# SCH_led_button_2026-04-28.net
KiCad netlist of a schematic drawn in EasyEDA
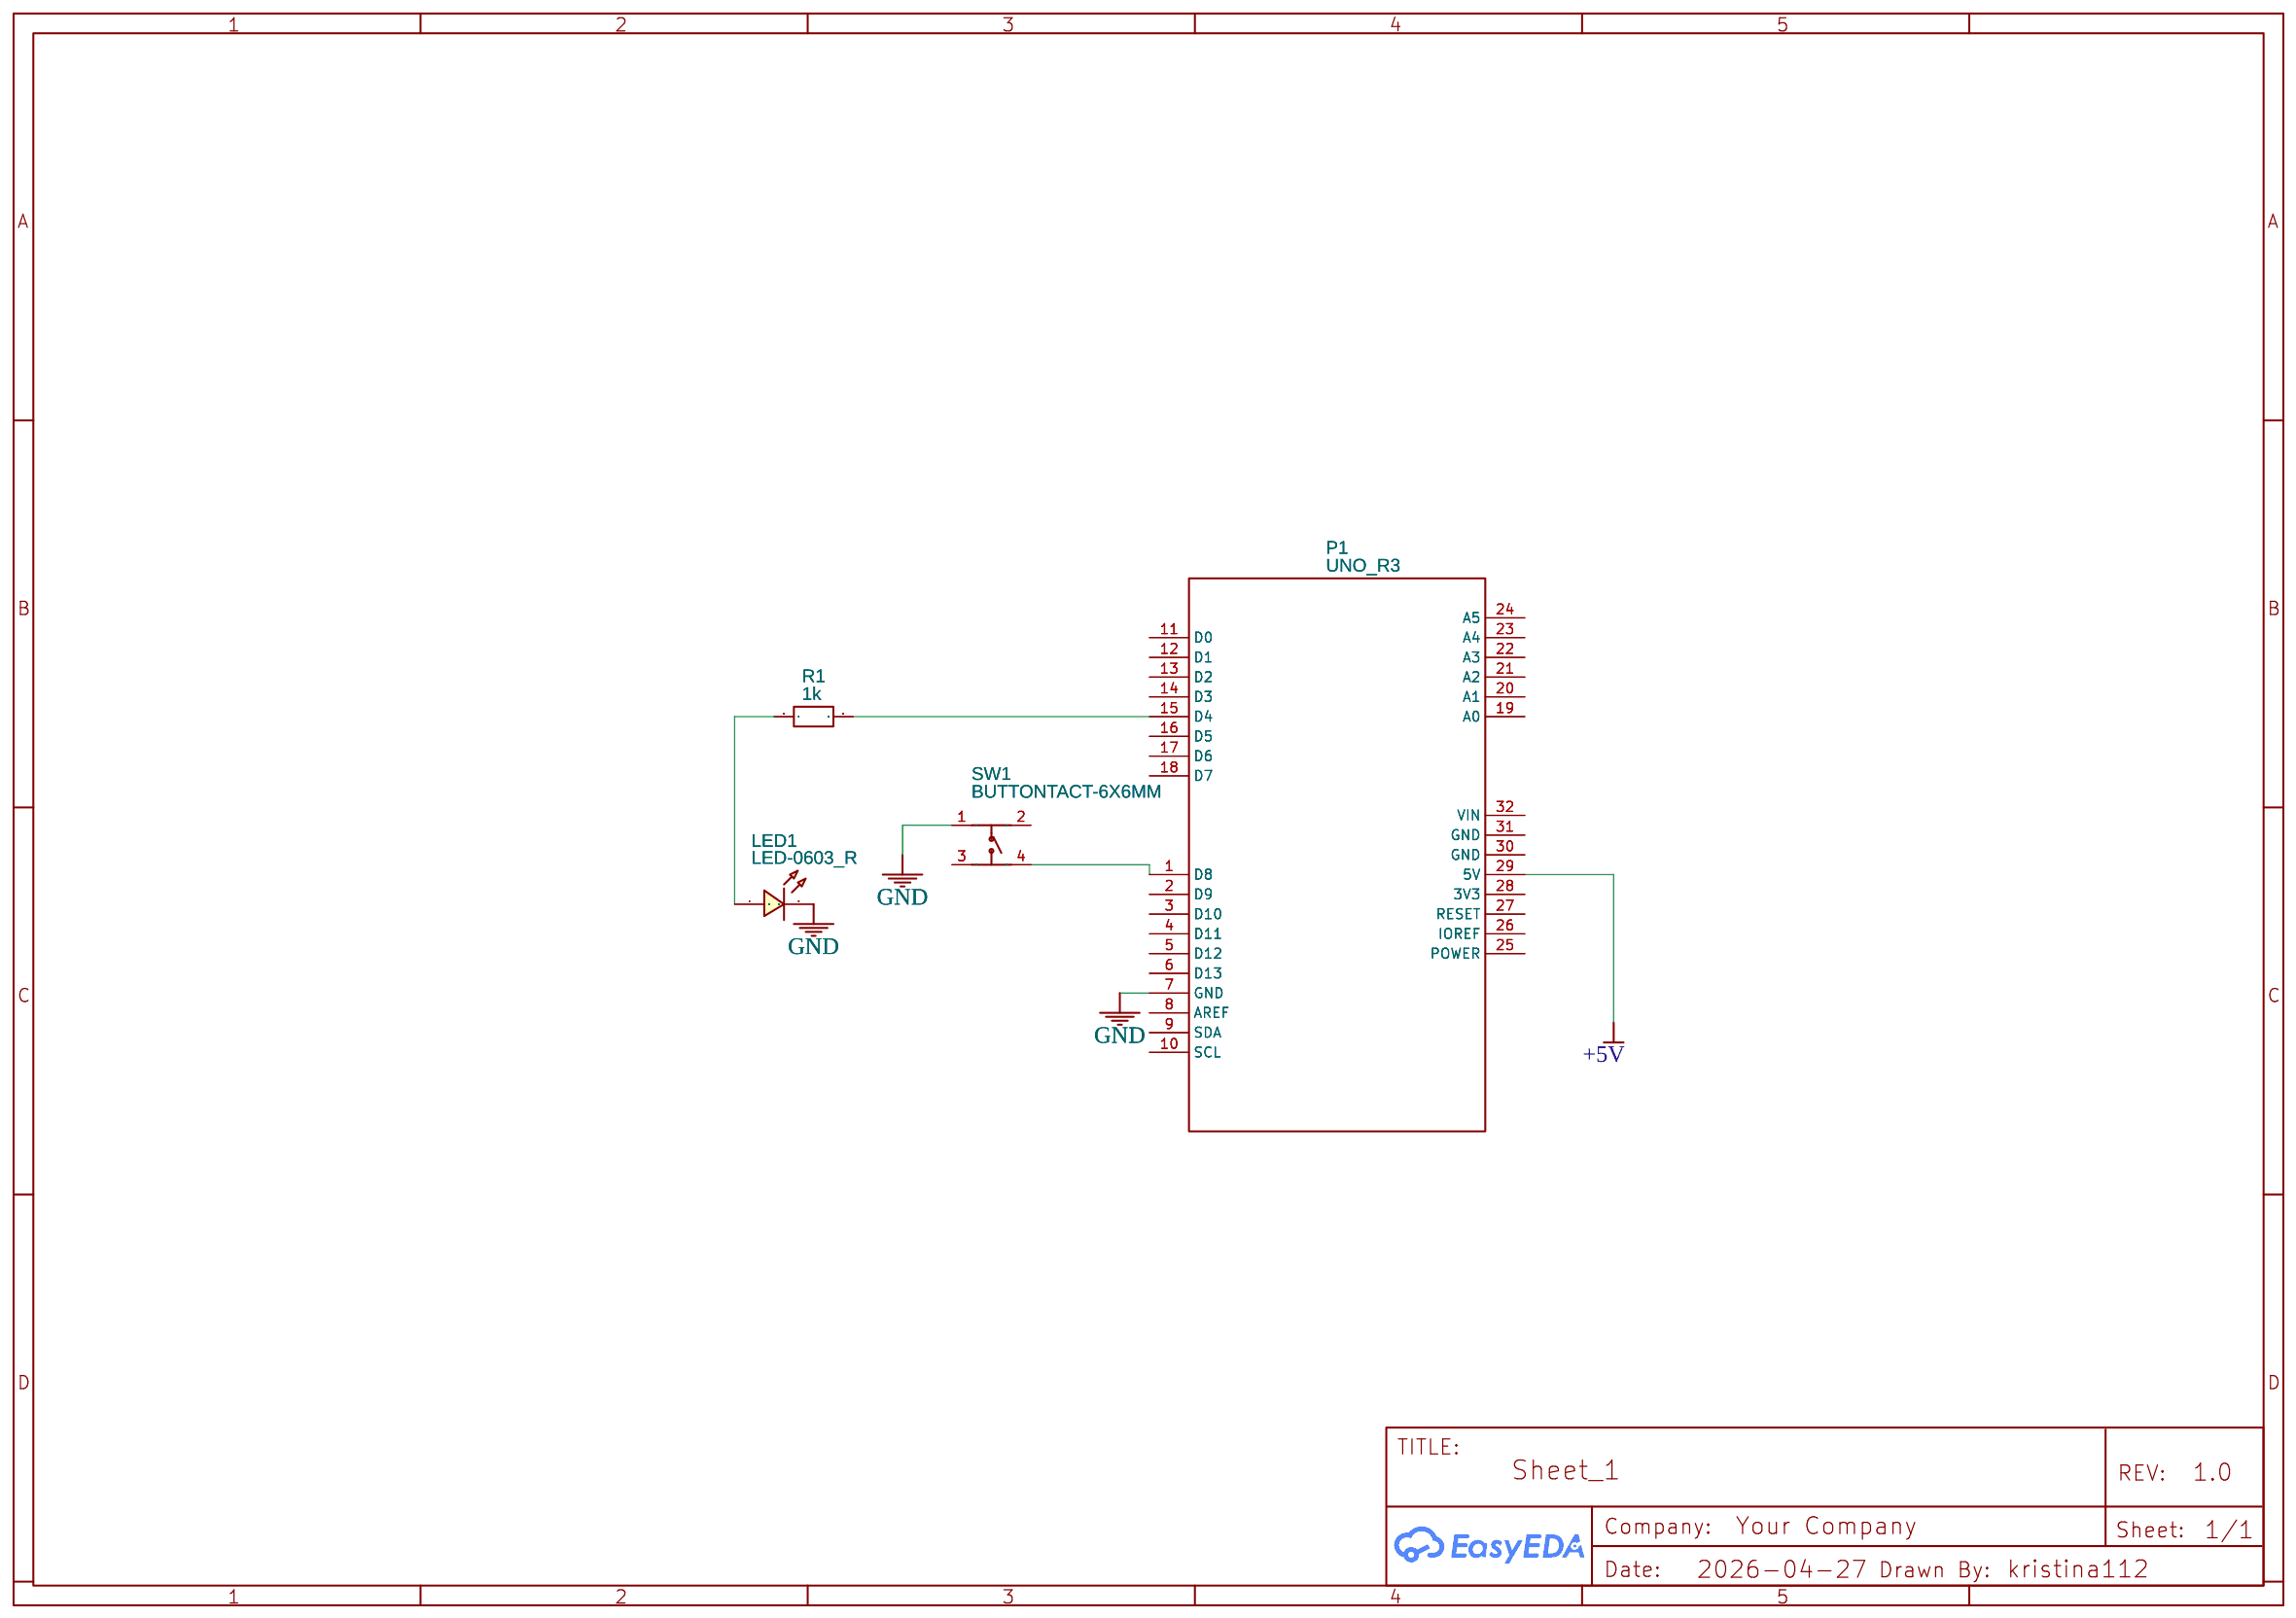
[diagram p0: schematic sheet]

(export (version "E")
  (design (tool "Eeschema 10.0.6"))
  (components
    (comp (ref "LED1")
      (value "LED-0603_R")
      (fields
        (field (name "Manufacturer Part") "19-217/R6C-AL1M2VY/3T")
        (field (name "Manufacturer") "EVERLIGHT(台湾亿光)")
      )
      (libsource (lib "") (part "LED-0603_R"))
    )
    (comp (ref "P1") (value "UNO_R3") (libsource (lib "") (part "UNO_R3")))
    (comp (ref "R1") (value "1k") (libsource (lib "") (part "R_0603_EU")))
    (comp (ref "SW1")
      (value "BUTTONTACT-6X6MM")
      (fields (field (name "Manufacturer Part") "Buttontact-6x6mm"))
      (libsource (lib "") (part "BUTTONTACT-6X6MM"))
    )
  )
  (nets
    (net (code "1") (name "+5V") (class "Default")
      (node (ref "P1") (pin "29") (pinfunction "5V_29") (pintype "unspecified"))
    )
    (net (code "2") (name "GND") (class "Default")
      (node (ref "LED1") (pin "2") (pinfunction "2_2") (pintype "unspecified"))
      (node (ref "P1") (pin "7") (pinfunction "GND_7") (pintype "unspecified"))
      (node (ref "SW1") (pin "1") (pinfunction "A_1") (pintype "unspecified"))
    )
    (net (code "3") (name "Net-(LED1-Pad1)") (class "Default")
      (node (ref "LED1") (pin "1") (pinfunction "1_1") (pintype "unspecified"))
      (node (ref "R1") (pin "1") (pinfunction "1_1") (pintype "unspecified"))
    )
    (net (code "4") (name "Net-(P1-D4)") (class "Default")
      (node (ref "P1") (pin "15") (pinfunction "D4_15") (pintype "unspecified"))
      (node (ref "R1") (pin "2") (pinfunction "2_2") (pintype "unspecified"))
    )
    (net (code "5") (name "Net-(P1-D8)") (class "Default")
      (node (ref "P1") (pin "1") (pinfunction "D8_1") (pintype "unspecified"))
      (node (ref "SW1") (pin "4") (pinfunction "D_4") (pintype "unspecified"))
    )
    (net (code "6") (name "unconnected-(P1-3V3-Pad28)") (class "Default")
      (node (ref "P1") (pin "28") (pinfunction "3V3_28") (pintype "unspecified"))
    )
    (net (code "7") (name "unconnected-(P1-A0-Pad19)") (class "Default")
      (node (ref "P1") (pin "19") (pinfunction "A0_19") (pintype "unspecified"))
    )
    (net (code "8") (name "unconnected-(P1-A1-Pad20)") (class "Default")
      (node (ref "P1") (pin "20") (pinfunction "A1_20") (pintype "unspecified"))
    )
    (net (code "9") (name "unconnected-(P1-A2-Pad21)") (class "Default")
      (node (ref "P1") (pin "21") (pinfunction "A2_21") (pintype "unspecified"))
    )
    (net (code "10") (name "unconnected-(P1-A3-Pad22)") (class "Default")
      (node (ref "P1") (pin "22") (pinfunction "A3_22") (pintype "unspecified"))
    )
    (net (code "11") (name "unconnected-(P1-A4-Pad23)") (class "Default")
      (node (ref "P1") (pin "23") (pinfunction "A4_23") (pintype "unspecified"))
    )
    (net (code "12") (name "unconnected-(P1-A5-Pad24)") (class "Default")
      (node (ref "P1") (pin "24") (pinfunction "A5_24") (pintype "unspecified"))
    )
    (net (code "13") (name "unconnected-(P1-AREF-Pad8)") (class "Default")
      (node (ref "P1") (pin "8") (pinfunction "AREF_8") (pintype "unspecified"))
    )
    (net (code "14") (name "unconnected-(P1-D0-Pad11)") (class "Default")
      (node (ref "P1") (pin "11") (pinfunction "D0_11") (pintype "unspecified"))
    )
    (net (code "15") (name "unconnected-(P1-D1-Pad12)") (class "Default")
      (node (ref "P1") (pin "12") (pinfunction "D1_12") (pintype "unspecified"))
    )
    (net (code "16") (name "unconnected-(P1-D2-Pad13)") (class "Default")
      (node (ref "P1") (pin "13") (pinfunction "D2_13") (pintype "unspecified"))
    )
    (net (code "17") (name "unconnected-(P1-D3-Pad14)") (class "Default")
      (node (ref "P1") (pin "14") (pinfunction "D3_14") (pintype "unspecified"))
    )
    (net (code "18") (name "unconnected-(P1-D5-Pad16)") (class "Default")
      (node (ref "P1") (pin "16") (pinfunction "D5_16") (pintype "unspecified"))
    )
    (net (code "19") (name "unconnected-(P1-D6-Pad17)") (class "Default")
      (node (ref "P1") (pin "17") (pinfunction "D6_17") (pintype "unspecified"))
    )
    (net (code "20") (name "unconnected-(P1-D7-Pad18)") (class "Default")
      (node (ref "P1") (pin "18") (pinfunction "D7_18") (pintype "unspecified"))
    )
    (net (code "21") (name "unconnected-(P1-D9-Pad2)") (class "Default")
      (node (ref "P1") (pin "2") (pinfunction "D9_2") (pintype "unspecified"))
    )
    (net (code "22") (name "unconnected-(P1-D10-Pad3)") (class "Default")
      (node (ref "P1") (pin "3") (pinfunction "D10_3") (pintype "unspecified"))
    )
    (net (code "23") (name "unconnected-(P1-D11-Pad4)") (class "Default")
      (node (ref "P1") (pin "4") (pinfunction "D11_4") (pintype "unspecified"))
    )
    (net (code "24") (name "unconnected-(P1-D12-Pad5)") (class "Default")
      (node (ref "P1") (pin "5") (pinfunction "D12_5") (pintype "unspecified"))
    )
    (net (code "25") (name "unconnected-(P1-D13-Pad6)") (class "Default")
      (node (ref "P1") (pin "6") (pinfunction "D13_6") (pintype "unspecified"))
    )
    (net (code "26") (name "unconnected-(P1-GND-Pad30)") (class "Default")
      (node (ref "P1") (pin "30") (pinfunction "GND_30") (pintype "unspecified"))
    )
    (net (code "27") (name "unconnected-(P1-GND-Pad31)") (class "Default")
      (node (ref "P1") (pin "31") (pinfunction "GND_31") (pintype "unspecified"))
    )
    (net (code "28") (name "unconnected-(P1-IOREF-Pad26)") (class "Default")
      (node (ref "P1") (pin "26") (pinfunction "IOREF_26") (pintype "unspecified"))
    )
    (net (code "29") (name "unconnected-(P1-POWER-Pad25)") (class "Default")
      (node (ref "P1") (pin "25") (pinfunction "POWER_25") (pintype "unspecified"))
    )
    (net (code "30") (name "unconnected-(P1-RESET-Pad27)") (class "Default")
      (node (ref "P1") (pin "27") (pinfunction "RESET_27") (pintype "unspecified"))
    )
    (net (code "31") (name "unconnected-(P1-SCL-Pad10)") (class "Default")
      (node (ref "P1") (pin "10") (pinfunction "SCL_10") (pintype "unspecified"))
    )
    (net (code "32") (name "unconnected-(P1-SDA-Pad9)") (class "Default")
      (node (ref "P1") (pin "9") (pinfunction "SDA_9") (pintype "unspecified"))
    )
    (net (code "33") (name "unconnected-(P1-VIN-Pad32)") (class "Default")
      (node (ref "P1") (pin "32") (pinfunction "VIN_32") (pintype "unspecified"))
    )
    (net (code "34") (name "unconnected-(SW1-B-Pad2)") (class "Default")
      (node (ref "SW1") (pin "2") (pinfunction "B_2") (pintype "unspecified"))
    )
    (net (code "35") (name "unconnected-(SW1-C-Pad3)") (class "Default")
      (node (ref "SW1") (pin "3") (pinfunction "C_3") (pintype "unspecified"))
    )
  )
)
